# HomeSenseProto.net
KiCad netlist of a schematic drawn in EAGLE
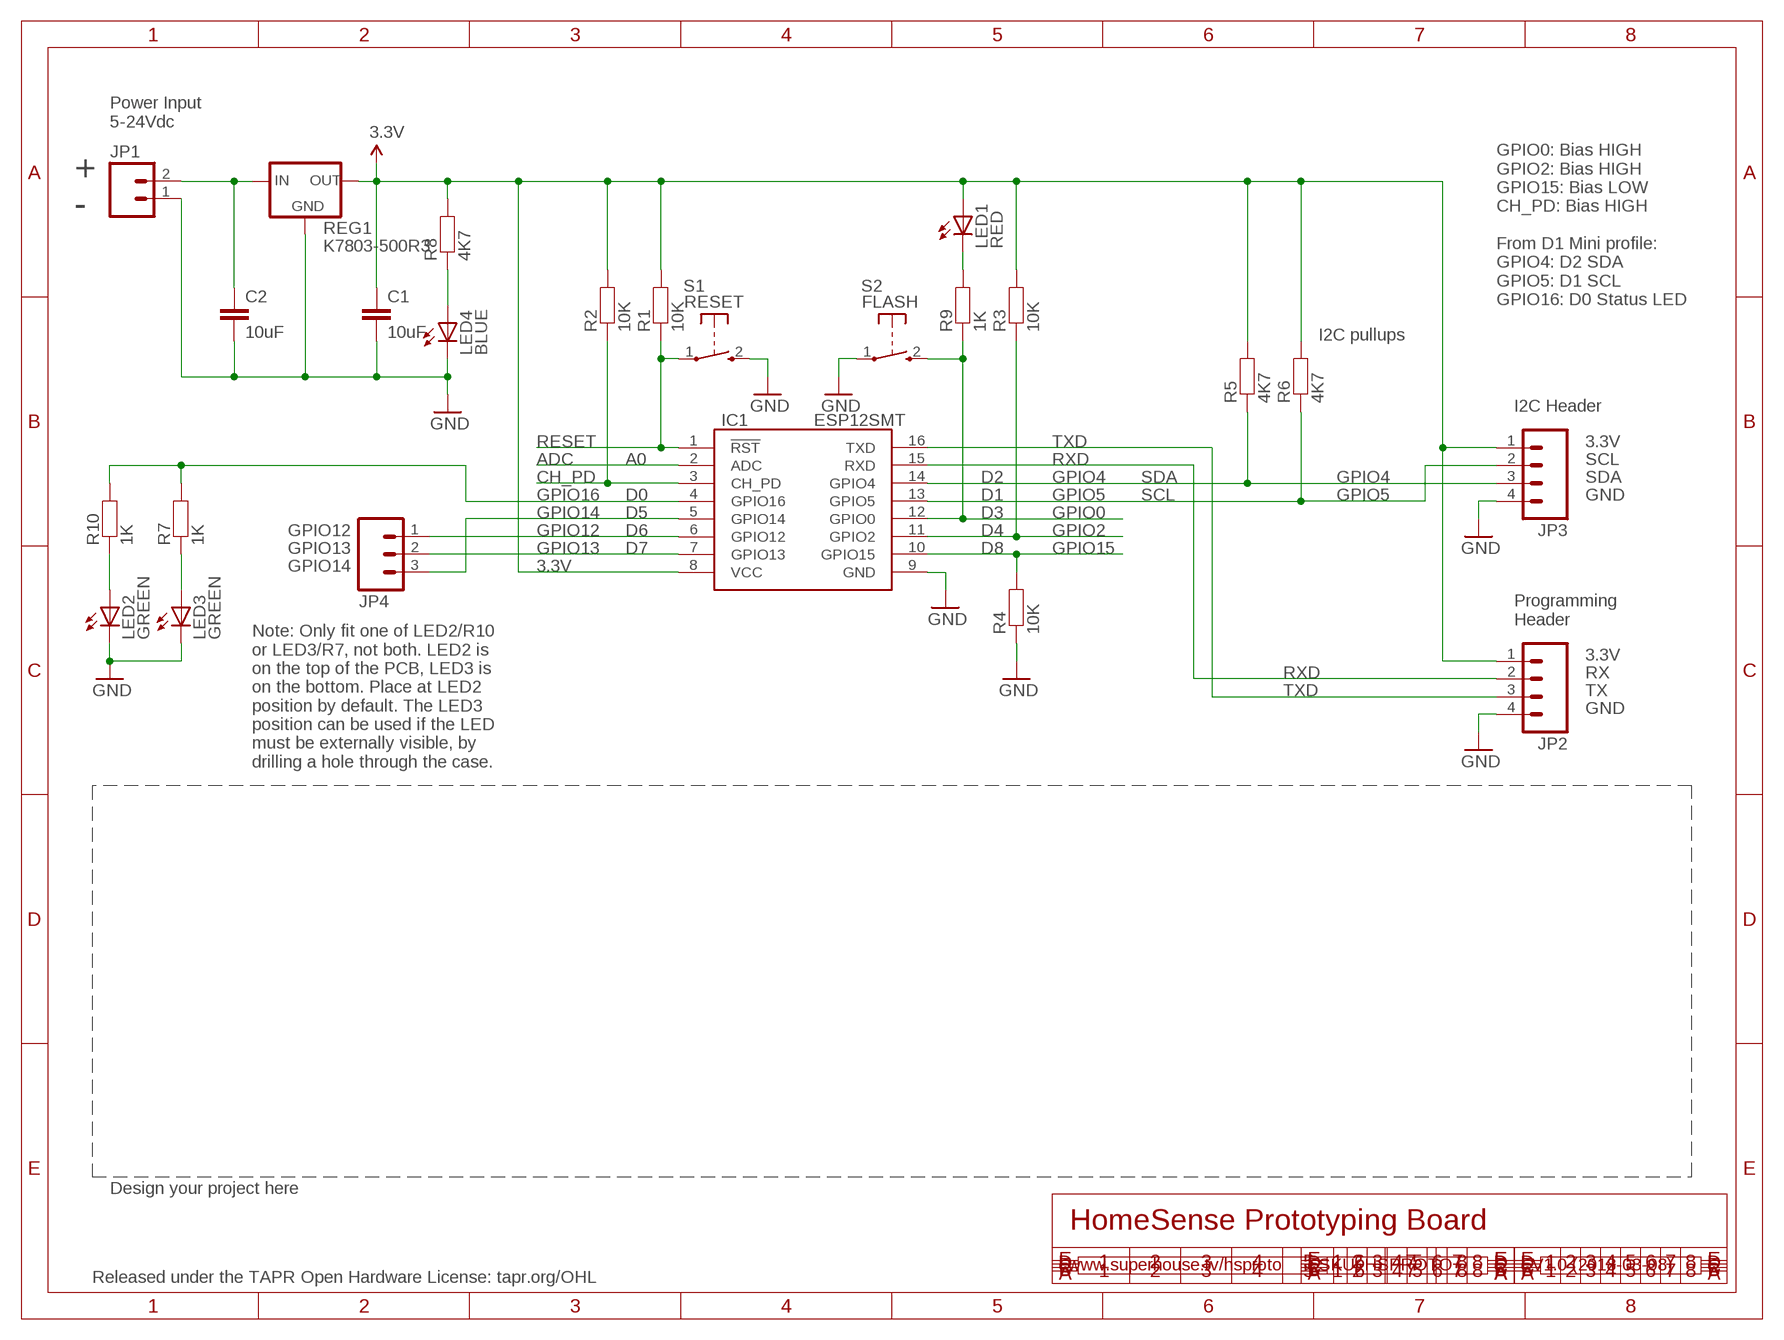
[diagram p0: schematic, sheet 1]

(export (version "E")
  (design (tool "Eeschema 10.0.6"))
  (components
    (comp (ref "C1")
      (value "10uF")
      (footprint "eagle-import:0805")
      (libsource (lib "eagle-import") (part "CAP0805"))
    )
    (comp (ref "C2")
      (value "10uF")
      (footprint "eagle-import:0805")
      (libsource (lib "eagle-import") (part "CAP0805"))
    )
    (comp (ref "IC1")
      (value "ESP12SMT")
      (footprint "eagle-import:ESP12")
      (libsource (lib "eagle-import") (part "ESP12SMT"))
    )
    (comp (ref "JP1")
      (value "M02PTH")
      (footprint "eagle-import:1X02")
      (libsource (lib "eagle-import") (part "M02PTH"))
    )
    (comp (ref "JP2")
      (value "M04PTH")
      (footprint "eagle-import:1X04")
      (libsource (lib "eagle-import") (part "M04PTH"))
    )
    (comp (ref "JP3")
      (value "M04PTH")
      (footprint "eagle-import:1X04")
      (libsource (lib "eagle-import") (part "M04PTH"))
    )
    (comp (ref "JP4")
      (value "M03PTH")
      (footprint "eagle-import:1X03")
      (libsource (lib "eagle-import") (part "M03PTH"))
    )
    (comp (ref "LED1")
      (value "RED")
      (footprint "eagle-import:LED-0603")
      (libsource (lib "eagle-import") (part "LED0603"))
    )
    (comp (ref "LED2")
      (value "GREEN")
      (footprint "eagle-import:LED-0603")
      (libsource (lib "eagle-import") (part "LED0603"))
    )
    (comp (ref "LED3")
      (value "GREEN")
      (footprint "eagle-import:LED-0603")
      (libsource (lib "eagle-import") (part "LED0603"))
    )
    (comp (ref "LED4")
      (value "BLUE")
      (footprint "eagle-import:LED-0603")
      (libsource (lib "eagle-import") (part "LED0603"))
    )
    (comp (ref "R1")
      (value "10K")
      (footprint "eagle-import:0603")
      (libsource (lib "eagle-import") (part "RESISTOR0603"))
    )
    (comp (ref "R2")
      (value "10K")
      (footprint "eagle-import:0603")
      (libsource (lib "eagle-import") (part "RESISTOR0603"))
    )
    (comp (ref "R3")
      (value "10K")
      (footprint "eagle-import:0603")
      (libsource (lib "eagle-import") (part "RESISTOR0603"))
    )
    (comp (ref "R4")
      (value "10K")
      (footprint "eagle-import:0603")
      (libsource (lib "eagle-import") (part "RESISTOR0603"))
    )
    (comp (ref "R5")
      (value "4K7")
      (footprint "eagle-import:0603")
      (libsource (lib "eagle-import") (part "RESISTOR0603"))
    )
    (comp (ref "R6")
      (value "4K7")
      (footprint "eagle-import:0603")
      (libsource (lib "eagle-import") (part "RESISTOR0603"))
    )
    (comp (ref "R7")
      (value "1K")
      (footprint "eagle-import:0603")
      (libsource (lib "eagle-import") (part "RESISTOR0603"))
    )
    (comp (ref "R8")
      (value "4K7")
      (footprint "eagle-import:0603")
      (libsource (lib "eagle-import") (part "RESISTOR0603"))
    )
    (comp (ref "R9")
      (value "1K")
      (footprint "eagle-import:0603")
      (libsource (lib "eagle-import") (part "RESISTOR0603"))
    )
    (comp (ref "R10")
      (value "1K")
      (footprint "eagle-import:0603")
      (libsource (lib "eagle-import") (part "RESISTOR0603"))
    )
    (comp (ref "REG1")
      (value "K7803-500R3")
      (footprint "eagle-import:K78XX-500R3")
      (libsource (lib "eagle-import") (part "K78XX-500R3"))
    )
    (comp (ref "S1")
      (value "RESET")
      (footprint "eagle-import:TACTILE_SWITCH_SMD_2PIN_TINY")
      (libsource (lib "eagle-import") (part "TAC_SWITCH_2PINSMT"))
    )
    (comp (ref "S2")
      (value "FLASH")
      (footprint "eagle-import:TACTILE_SWITCH_SMD_2PIN_TINY")
      (libsource (lib "eagle-import") (part "TAC_SWITCH_2PINSMT"))
    )
  )
  (nets
    (net (code "1") (name "/ADC") (class "Default")
      (node (ref "IC1") (pin "2") (pinfunction "ADC_2") (pintype "input"))
    )
    (net (code "2") (name "/CH_PD") (class "Default")
      (node (ref "IC1") (pin "3") (pinfunction "CH_PD_3") (pintype "input"))
      (node (ref "R2") (pin "1") (pinfunction "1_1") (pintype "passive"))
    )
    (net (code "3") (name "/GPIO0") (class "Default")
      (node (ref "IC1") (pin "12") (pinfunction "GPIO0_12") (pintype "bidirectional"))
      (node (ref "R9") (pin "1") (pinfunction "1_1") (pintype "passive"))
      (node (ref "S2") (pin "2") (pinfunction "S_2") (pintype "passive"))
    )
    (net (code "4") (name "/GPIO2") (class "Default")
      (node (ref "IC1") (pin "11") (pinfunction "GPIO2_11") (pintype "bidirectional"))
      (node (ref "R3") (pin "1") (pinfunction "1_1") (pintype "passive"))
    )
    (net (code "5") (name "/GPIO4") (class "Default")
      (node (ref "IC1") (pin "14") (pinfunction "GPIO4_14") (pintype "bidirectional"))
      (node (ref "JP3") (pin "3") (pinfunction "3_3") (pintype "passive"))
      (node (ref "R5") (pin "1") (pinfunction "1_1") (pintype "passive"))
    )
    (net (code "6") (name "/GPIO5") (class "Default")
      (node (ref "IC1") (pin "13") (pinfunction "GPIO5_13") (pintype "bidirectional"))
      (node (ref "JP3") (pin "2") (pinfunction "2_2") (pintype "passive"))
      (node (ref "R6") (pin "1") (pinfunction "1_1") (pintype "passive"))
    )
    (net (code "7") (name "/GPIO12") (class "Default")
      (node (ref "IC1") (pin "6") (pinfunction "GPIO12_6") (pintype "bidirectional"))
      (node (ref "JP4") (pin "1") (pinfunction "1_1") (pintype "passive"))
    )
    (net (code "8") (name "/GPIO13") (class "Default")
      (node (ref "IC1") (pin "7") (pinfunction "GPIO13_7") (pintype "bidirectional"))
      (node (ref "JP4") (pin "2") (pinfunction "2_2") (pintype "passive"))
    )
    (net (code "9") (name "/GPIO14") (class "Default")
      (node (ref "IC1") (pin "5") (pinfunction "GPIO14_5") (pintype "bidirectional"))
      (node (ref "JP4") (pin "3") (pinfunction "3_3") (pintype "passive"))
    )
    (net (code "10") (name "/GPIO15") (class "Default")
      (node (ref "IC1") (pin "10") (pinfunction "GPIO15_10") (pintype "bidirectional"))
      (node (ref "R4") (pin "2") (pinfunction "2_2") (pintype "passive"))
    )
    (net (code "11") (name "/GPIO16") (class "Default")
      (node (ref "IC1") (pin "4") (pinfunction "GPIO16_4") (pintype "bidirectional"))
      (node (ref "R10") (pin "2") (pinfunction "2_2") (pintype "passive"))
      (node (ref "R7") (pin "2") (pinfunction "2_2") (pintype "passive"))
    )
    (net (code "12") (name "/RESET") (class "Default")
      (node (ref "IC1") (pin "1") (pinfunction "~{RST}_1") (pintype "bidirectional"))
      (node (ref "R1") (pin "1") (pinfunction "1_1") (pintype "passive"))
      (node (ref "S1") (pin "1") (pinfunction "P_1") (pintype "passive"))
    )
    (net (code "13") (name "/RXD") (class "Default")
      (node (ref "IC1") (pin "15") (pinfunction "RXD_15") (pintype "input"))
      (node (ref "JP2") (pin "2") (pinfunction "2_2") (pintype "passive"))
    )
    (net (code "14") (name "/TXD") (class "Default")
      (node (ref "IC1") (pin "16") (pinfunction "TXD_16") (pintype "output"))
      (node (ref "JP2") (pin "3") (pinfunction "3_3") (pintype "passive"))
    )
    (net (code "15") (name "3.3V") (class "Default")
      (node (ref "C1") (pin "1") (pinfunction "1_1") (pintype "passive"))
      (node (ref "IC1") (pin "8") (pinfunction "VCC_8") (pintype "power_in"))
      (node (ref "JP2") (pin "1") (pinfunction "1_1") (pintype "passive"))
      (node (ref "JP3") (pin "1") (pinfunction "1_1") (pintype "passive"))
      (node (ref "LED1") (pin "A") (pinfunction "A_A") (pintype "passive"))
      (node (ref "R1") (pin "2") (pinfunction "2_2") (pintype "passive"))
      (node (ref "R2") (pin "2") (pinfunction "2_2") (pintype "passive"))
      (node (ref "R3") (pin "2") (pinfunction "2_2") (pintype "passive"))
      (node (ref "R5") (pin "2") (pinfunction "2_2") (pintype "passive"))
      (node (ref "R6") (pin "2") (pinfunction "2_2") (pintype "passive"))
      (node (ref "R8") (pin "2") (pinfunction "2_2") (pintype "passive"))
      (node (ref "REG1") (pin "3") (pinfunction "OUT_3") (pintype "output"))
    )
    (net (code "16") (name "GND") (class "Default")
      (node (ref "C1") (pin "2") (pinfunction "2_2") (pintype "passive"))
      (node (ref "C2") (pin "2") (pinfunction "2_2") (pintype "passive"))
      (node (ref "IC1") (pin "9") (pinfunction "GND_9") (pintype "power_in"))
      (node (ref "JP1") (pin "1") (pinfunction "1_1") (pintype "passive"))
      (node (ref "JP2") (pin "4") (pinfunction "4_4") (pintype "passive"))
      (node (ref "JP3") (pin "4") (pinfunction "4_4") (pintype "passive"))
      (node (ref "LED2") (pin "C") (pinfunction "C_C") (pintype "passive"))
      (node (ref "LED3") (pin "C") (pinfunction "C_C") (pintype "passive"))
      (node (ref "LED4") (pin "C") (pinfunction "C_C") (pintype "passive"))
      (node (ref "R4") (pin "1") (pinfunction "1_1") (pintype "passive"))
      (node (ref "REG1") (pin "2") (pinfunction "GND_2") (pintype "input"))
      (node (ref "S1") (pin "2") (pinfunction "S_2") (pintype "passive"))
      (node (ref "S2") (pin "1") (pinfunction "P_1") (pintype "passive"))
    )
    (net (code "17") (name "Net-(LED1-PadC)") (class "Default")
      (node (ref "LED1") (pin "C") (pinfunction "C_C") (pintype "passive"))
      (node (ref "R9") (pin "2") (pinfunction "2_2") (pintype "passive"))
    )
    (net (code "18") (name "Net-(LED2-PadA)") (class "Default")
      (node (ref "LED2") (pin "A") (pinfunction "A_A") (pintype "passive"))
      (node (ref "R10") (pin "1") (pinfunction "1_1") (pintype "passive"))
    )
    (net (code "19") (name "Net-(LED3-PadA)") (class "Default")
      (node (ref "LED3") (pin "A") (pinfunction "A_A") (pintype "passive"))
      (node (ref "R7") (pin "1") (pinfunction "1_1") (pintype "passive"))
    )
    (net (code "20") (name "Net-(LED4-PadA)") (class "Default")
      (node (ref "LED4") (pin "A") (pinfunction "A_A") (pintype "passive"))
      (node (ref "R8") (pin "1") (pinfunction "1_1") (pintype "passive"))
    )
    (net (code "21") (name "Net-(REG1-IN)") (class "Default")
      (node (ref "C2") (pin "1") (pinfunction "1_1") (pintype "passive"))
      (node (ref "JP1") (pin "2") (pinfunction "2_2") (pintype "passive"))
      (node (ref "REG1") (pin "1") (pinfunction "IN_1") (pintype "input"))
    )
  )
)
